# KeyMatrixRev2.net
KiCad netlist of a schematic drawn in Altium Designer
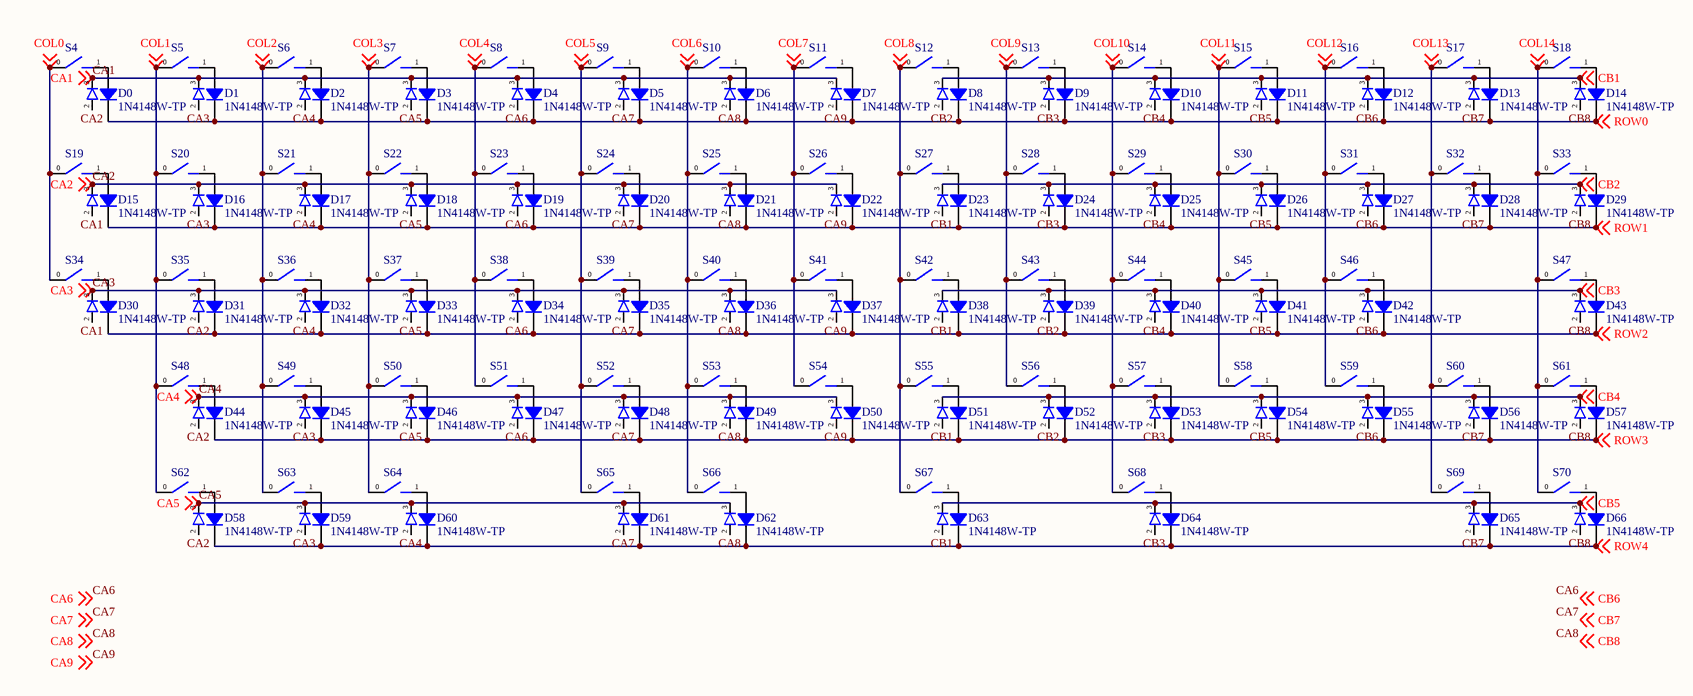
[diagram p0: KeyMatrixRev2.SchDoc]

(export (version "E")
  (design (tool "Eeschema 10.0.6"))
  (components
    (comp (ref "D0")
      (value "1N4148W-TP")
      (footprint "SOD-123")
      (description "DIODE GEN PURP 100V 150MA SOD123")
      (fields (field (name "MANUFACTURER") "Micro Commercial Co"))
      (libsource (lib "Celestial Altium Library - altium_library") (part "Diode"))
    )
    (comp (ref "D1")
      (value "1N4148W-TP")
      (footprint "SOD-123")
      (description "DIODE GEN PURP 100V 150MA SOD123")
      (fields (field (name "MANUFACTURER") "Micro Commercial Co"))
      (libsource (lib "Celestial Altium Library - altium_library") (part "Diode"))
    )
    (comp (ref "D2")
      (value "1N4148W-TP")
      (footprint "SOD-123")
      (description "DIODE GEN PURP 100V 150MA SOD123")
      (fields (field (name "MANUFACTURER") "Micro Commercial Co"))
      (libsource (lib "Celestial Altium Library - altium_library") (part "Diode"))
    )
    (comp (ref "D3")
      (value "1N4148W-TP")
      (footprint "SOD-123")
      (description "DIODE GEN PURP 100V 150MA SOD123")
      (fields (field (name "MANUFACTURER") "Micro Commercial Co"))
      (libsource (lib "Celestial Altium Library - altium_library") (part "Diode"))
    )
    (comp (ref "D4")
      (value "1N4148W-TP")
      (footprint "SOD-123")
      (description "DIODE GEN PURP 100V 150MA SOD123")
      (fields (field (name "MANUFACTURER") "Micro Commercial Co"))
      (libsource (lib "Celestial Altium Library - altium_library") (part "Diode"))
    )
    (comp (ref "D5")
      (value "1N4148W-TP")
      (footprint "SOD-123")
      (description "DIODE GEN PURP 100V 150MA SOD123")
      (fields (field (name "MANUFACTURER") "Micro Commercial Co"))
      (libsource (lib "Celestial Altium Library - altium_library") (part "Diode"))
    )
    (comp (ref "D6")
      (value "1N4148W-TP")
      (footprint "SOD-123")
      (description "DIODE GEN PURP 100V 150MA SOD123")
      (fields (field (name "MANUFACTURER") "Micro Commercial Co"))
      (libsource (lib "Celestial Altium Library - altium_library") (part "Diode"))
    )
    (comp (ref "D7")
      (value "1N4148W-TP")
      (footprint "SOD-123")
      (description "DIODE GEN PURP 100V 150MA SOD123")
      (fields (field (name "MANUFACTURER") "Micro Commercial Co"))
      (libsource (lib "Celestial Altium Library - altium_library") (part "Diode"))
    )
    (comp (ref "D8")
      (value "1N4148W-TP")
      (footprint "SOD-123")
      (description "DIODE GEN PURP 100V 150MA SOD123")
      (fields (field (name "MANUFACTURER") "Micro Commercial Co"))
      (libsource (lib "Celestial Altium Library - altium_library") (part "Diode"))
    )
    (comp (ref "D9")
      (value "1N4148W-TP")
      (footprint "SOD-123")
      (description "DIODE GEN PURP 100V 150MA SOD123")
      (fields (field (name "MANUFACTURER") "Micro Commercial Co"))
      (libsource (lib "Celestial Altium Library - altium_library") (part "Diode"))
    )
    (comp (ref "D10")
      (value "1N4148W-TP")
      (footprint "SOD-123")
      (description "DIODE GEN PURP 100V 150MA SOD123")
      (fields (field (name "MANUFACTURER") "Micro Commercial Co"))
      (libsource (lib "Celestial Altium Library - altium_library") (part "Diode"))
    )
    (comp (ref "D11")
      (value "1N4148W-TP")
      (footprint "SOD-123")
      (description "DIODE GEN PURP 100V 150MA SOD123")
      (fields (field (name "MANUFACTURER") "Micro Commercial Co"))
      (libsource (lib "Celestial Altium Library - altium_library") (part "Diode"))
    )
    (comp (ref "D12")
      (value "1N4148W-TP")
      (footprint "SOD-123")
      (description "DIODE GEN PURP 100V 150MA SOD123")
      (fields (field (name "MANUFACTURER") "Micro Commercial Co"))
      (libsource (lib "Celestial Altium Library - altium_library") (part "Diode"))
    )
    (comp (ref "D13")
      (value "1N4148W-TP")
      (footprint "SOD-123")
      (description "DIODE GEN PURP 100V 150MA SOD123")
      (fields (field (name "MANUFACTURER") "Micro Commercial Co"))
      (libsource (lib "Celestial Altium Library - altium_library") (part "Diode"))
    )
    (comp (ref "D14")
      (value "1N4148W-TP")
      (footprint "SOD-123")
      (description "DIODE GEN PURP 100V 150MA SOD123")
      (fields (field (name "MANUFACTURER") "Micro Commercial Co"))
      (libsource (lib "Celestial Altium Library - altium_library") (part "Diode"))
    )
    (comp (ref "D15")
      (value "1N4148W-TP")
      (footprint "SOD-123")
      (description "DIODE GEN PURP 100V 150MA SOD123")
      (fields (field (name "MANUFACTURER") "Micro Commercial Co"))
      (libsource (lib "Celestial Altium Library - altium_library") (part "Diode"))
    )
    (comp (ref "D16")
      (value "1N4148W-TP")
      (footprint "SOD-123")
      (description "DIODE GEN PURP 100V 150MA SOD123")
      (fields (field (name "MANUFACTURER") "Micro Commercial Co"))
      (libsource (lib "Celestial Altium Library - altium_library") (part "Diode"))
    )
    (comp (ref "D17")
      (value "1N4148W-TP")
      (footprint "SOD-123")
      (description "DIODE GEN PURP 100V 150MA SOD123")
      (fields (field (name "MANUFACTURER") "Micro Commercial Co"))
      (libsource (lib "Celestial Altium Library - altium_library") (part "Diode"))
    )
    (comp (ref "D18")
      (value "1N4148W-TP")
      (footprint "SOD-123")
      (description "DIODE GEN PURP 100V 150MA SOD123")
      (fields (field (name "MANUFACTURER") "Micro Commercial Co"))
      (libsource (lib "Celestial Altium Library - altium_library") (part "Diode"))
    )
    (comp (ref "D19")
      (value "1N4148W-TP")
      (footprint "SOD-123")
      (description "DIODE GEN PURP 100V 150MA SOD123")
      (fields (field (name "MANUFACTURER") "Micro Commercial Co"))
      (libsource (lib "Celestial Altium Library - altium_library") (part "Diode"))
    )
    (comp (ref "D20")
      (value "1N4148W-TP")
      (footprint "SOD-123")
      (description "DIODE GEN PURP 100V 150MA SOD123")
      (fields (field (name "MANUFACTURER") "Micro Commercial Co"))
      (libsource (lib "Celestial Altium Library - altium_library") (part "Diode"))
    )
    (comp (ref "D21")
      (value "1N4148W-TP")
      (footprint "SOD-123")
      (description "DIODE GEN PURP 100V 150MA SOD123")
      (fields (field (name "MANUFACTURER") "Micro Commercial Co"))
      (libsource (lib "Celestial Altium Library - altium_library") (part "Diode"))
    )
    (comp (ref "D22")
      (value "1N4148W-TP")
      (footprint "SOD-123")
      (description "DIODE GEN PURP 100V 150MA SOD123")
      (fields (field (name "MANUFACTURER") "Micro Commercial Co"))
      (libsource (lib "Celestial Altium Library - altium_library") (part "Diode"))
    )
    (comp (ref "D23")
      (value "1N4148W-TP")
      (footprint "SOD-123")
      (description "DIODE GEN PURP 100V 150MA SOD123")
      (fields (field (name "MANUFACTURER") "Micro Commercial Co"))
      (libsource (lib "Celestial Altium Library - altium_library") (part "Diode"))
    )
    (comp (ref "D24")
      (value "1N4148W-TP")
      (footprint "SOD-123")
      (description "DIODE GEN PURP 100V 150MA SOD123")
      (fields (field (name "MANUFACTURER") "Micro Commercial Co"))
      (libsource (lib "Celestial Altium Library - altium_library") (part "Diode"))
    )
    (comp (ref "D25")
      (value "1N4148W-TP")
      (footprint "SOD-123")
      (description "DIODE GEN PURP 100V 150MA SOD123")
      (fields (field (name "MANUFACTURER") "Micro Commercial Co"))
      (libsource (lib "Celestial Altium Library - altium_library") (part "Diode"))
    )
    (comp (ref "D26")
      (value "1N4148W-TP")
      (footprint "SOD-123")
      (description "DIODE GEN PURP 100V 150MA SOD123")
      (fields (field (name "MANUFACTURER") "Micro Commercial Co"))
      (libsource (lib "Celestial Altium Library - altium_library") (part "Diode"))
    )
    (comp (ref "D27")
      (value "1N4148W-TP")
      (footprint "SOD-123")
      (description "DIODE GEN PURP 100V 150MA SOD123")
      (fields (field (name "MANUFACTURER") "Micro Commercial Co"))
      (libsource (lib "Celestial Altium Library - altium_library") (part "Diode"))
    )
    (comp (ref "D28")
      (value "1N4148W-TP")
      (footprint "SOD-123")
      (description "DIODE GEN PURP 100V 150MA SOD123")
      (fields (field (name "MANUFACTURER") "Micro Commercial Co"))
      (libsource (lib "Celestial Altium Library - altium_library") (part "Diode"))
    )
    (comp (ref "D29")
      (value "1N4148W-TP")
      (footprint "SOD-123")
      (description "DIODE GEN PURP 100V 150MA SOD123")
      (fields (field (name "MANUFACTURER") "Micro Commercial Co"))
      (libsource (lib "Celestial Altium Library - altium_library") (part "Diode"))
    )
    (comp (ref "D30")
      (value "1N4148W-TP")
      (footprint "SOD-123")
      (description "DIODE GEN PURP 100V 150MA SOD123")
      (fields (field (name "MANUFACTURER") "Micro Commercial Co"))
      (libsource (lib "Celestial Altium Library - altium_library") (part "Diode"))
    )
    (comp (ref "D31")
      (value "1N4148W-TP")
      (footprint "SOD-123")
      (description "DIODE GEN PURP 100V 150MA SOD123")
      (fields (field (name "MANUFACTURER") "Micro Commercial Co"))
      (libsource (lib "Celestial Altium Library - altium_library") (part "Diode"))
    )
    (comp (ref "D32")
      (value "1N4148W-TP")
      (footprint "SOD-123")
      (description "DIODE GEN PURP 100V 150MA SOD123")
      (fields (field (name "MANUFACTURER") "Micro Commercial Co"))
      (libsource (lib "Celestial Altium Library - altium_library") (part "Diode"))
    )
    (comp (ref "D33")
      (value "1N4148W-TP")
      (footprint "SOD-123")
      (description "DIODE GEN PURP 100V 150MA SOD123")
      (fields (field (name "MANUFACTURER") "Micro Commercial Co"))
      (libsource (lib "Celestial Altium Library - altium_library") (part "Diode"))
    )
    (comp (ref "D34")
      (value "1N4148W-TP")
      (footprint "SOD-123")
      (description "DIODE GEN PURP 100V 150MA SOD123")
      (fields (field (name "MANUFACTURER") "Micro Commercial Co"))
      (libsource (lib "Celestial Altium Library - altium_library") (part "Diode"))
    )
    (comp (ref "D35")
      (value "1N4148W-TP")
      (footprint "SOD-123")
      (description "DIODE GEN PURP 100V 150MA SOD123")
      (fields (field (name "MANUFACTURER") "Micro Commercial Co"))
      (libsource (lib "Celestial Altium Library - altium_library") (part "Diode"))
    )
    (comp (ref "D36")
      (value "1N4148W-TP")
      (footprint "SOD-123")
      (description "DIODE GEN PURP 100V 150MA SOD123")
      (fields (field (name "MANUFACTURER") "Micro Commercial Co"))
      (libsource (lib "Celestial Altium Library - altium_library") (part "Diode"))
    )
    (comp (ref "D37")
      (value "1N4148W-TP")
      (footprint "SOD-123")
      (description "DIODE GEN PURP 100V 150MA SOD123")
      (fields (field (name "MANUFACTURER") "Micro Commercial Co"))
      (libsource (lib "Celestial Altium Library - altium_library") (part "Diode"))
    )
    (comp (ref "D38")
      (value "1N4148W-TP")
      (footprint "SOD-123")
      (description "DIODE GEN PURP 100V 150MA SOD123")
      (fields (field (name "MANUFACTURER") "Micro Commercial Co"))
      (libsource (lib "Celestial Altium Library - altium_library") (part "Diode"))
    )
    (comp (ref "D39")
      (value "1N4148W-TP")
      (footprint "SOD-123")
      (description "DIODE GEN PURP 100V 150MA SOD123")
      (fields (field (name "MANUFACTURER") "Micro Commercial Co"))
      (libsource (lib "Celestial Altium Library - altium_library") (part "Diode"))
    )
    (comp (ref "D40")
      (value "1N4148W-TP")
      (footprint "SOD-123")
      (description "DIODE GEN PURP 100V 150MA SOD123")
      (fields (field (name "MANUFACTURER") "Micro Commercial Co"))
      (libsource (lib "Celestial Altium Library - altium_library") (part "Diode"))
    )
    (comp (ref "D41")
      (value "1N4148W-TP")
      (footprint "SOD-123")
      (description "DIODE GEN PURP 100V 150MA SOD123")
      (fields (field (name "MANUFACTURER") "Micro Commercial Co"))
      (libsource (lib "Celestial Altium Library - altium_library") (part "Diode"))
    )
    (comp (ref "D42")
      (value "1N4148W-TP")
      (footprint "SOD-123")
      (description "DIODE GEN PURP 100V 150MA SOD123")
      (fields (field (name "MANUFACTURER") "Micro Commercial Co"))
      (libsource (lib "Celestial Altium Library - altium_library") (part "Diode"))
    )
    (comp (ref "D43")
      (value "1N4148W-TP")
      (footprint "SOD-123")
      (description "DIODE GEN PURP 100V 150MA SOD123")
      (fields (field (name "MANUFACTURER") "Micro Commercial Co"))
      (libsource (lib "Celestial Altium Library - altium_library") (part "Diode"))
    )
    (comp (ref "D44")
      (value "1N4148W-TP")
      (footprint "SOD-123")
      (description "DIODE GEN PURP 100V 150MA SOD123")
      (fields (field (name "MANUFACTURER") "Micro Commercial Co"))
      (libsource (lib "Celestial Altium Library - altium_library") (part "Diode"))
    )
    (comp (ref "D45")
      (value "1N4148W-TP")
      (footprint "SOD-123")
      (description "DIODE GEN PURP 100V 150MA SOD123")
      (fields (field (name "MANUFACTURER") "Micro Commercial Co"))
      (libsource (lib "Celestial Altium Library - altium_library") (part "Diode"))
    )
    (comp (ref "D46")
      (value "1N4148W-TP")
      (footprint "SOD-123")
      (description "DIODE GEN PURP 100V 150MA SOD123")
      (fields (field (name "MANUFACTURER") "Micro Commercial Co"))
      (libsource (lib "Celestial Altium Library - altium_library") (part "Diode"))
    )
    (comp (ref "D47")
      (value "1N4148W-TP")
      (footprint "SOD-123")
      (description "DIODE GEN PURP 100V 150MA SOD123")
      (fields (field (name "MANUFACTURER") "Micro Commercial Co"))
      (libsource (lib "Celestial Altium Library - altium_library") (part "Diode"))
    )
    (comp (ref "D48")
      (value "1N4148W-TP")
      (footprint "SOD-123")
      (description "DIODE GEN PURP 100V 150MA SOD123")
      (fields (field (name "MANUFACTURER") "Micro Commercial Co"))
      (libsource (lib "Celestial Altium Library - altium_library") (part "Diode"))
    )
    (comp (ref "D49")
      (value "1N4148W-TP")
      (footprint "SOD-123")
      (description "DIODE GEN PURP 100V 150MA SOD123")
      (fields (field (name "MANUFACTURER") "Micro Commercial Co"))
      (libsource (lib "Celestial Altium Library - altium_library") (part "Diode"))
    )
    (comp (ref "D50")
      (value "1N4148W-TP")
      (footprint "SOD-123")
      (description "DIODE GEN PURP 100V 150MA SOD123")
      (fields (field (name "MANUFACTURER") "Micro Commercial Co"))
      (libsource (lib "Celestial Altium Library - altium_library") (part "Diode"))
    )
    (comp (ref "D51")
      (value "1N4148W-TP")
      (footprint "SOD-123")
      (description "DIODE GEN PURP 100V 150MA SOD123")
      (fields (field (name "MANUFACTURER") "Micro Commercial Co"))
      (libsource (lib "Celestial Altium Library - altium_library") (part "Diode"))
    )
    (comp (ref "D52")
      (value "1N4148W-TP")
      (footprint "SOD-123")
      (description "DIODE GEN PURP 100V 150MA SOD123")
      (fields (field (name "MANUFACTURER") "Micro Commercial Co"))
      (libsource (lib "Celestial Altium Library - altium_library") (part "Diode"))
    )
    (comp (ref "D53")
      (value "1N4148W-TP")
      (footprint "SOD-123")
      (description "DIODE GEN PURP 100V 150MA SOD123")
      (fields (field (name "MANUFACTURER") "Micro Commercial Co"))
      (libsource (lib "Celestial Altium Library - altium_library") (part "Diode"))
    )
    (comp (ref "D54")
      (value "1N4148W-TP")
      (footprint "SOD-123")
      (description "DIODE GEN PURP 100V 150MA SOD123")
      (fields (field (name "MANUFACTURER") "Micro Commercial Co"))
      (libsource (lib "Celestial Altium Library - altium_library") (part "Diode"))
    )
    (comp (ref "D55")
      (value "1N4148W-TP")
      (footprint "SOD-123")
      (description "DIODE GEN PURP 100V 150MA SOD123")
      (fields (field (name "MANUFACTURER") "Micro Commercial Co"))
      (libsource (lib "Celestial Altium Library - altium_library") (part "Diode"))
    )
    (comp (ref "D56")
      (value "1N4148W-TP")
      (footprint "SOD-123")
      (description "DIODE GEN PURP 100V 150MA SOD123")
      (fields (field (name "MANUFACTURER") "Micro Commercial Co"))
      (libsource (lib "Celestial Altium Library - altium_library") (part "Diode"))
    )
    (comp (ref "D57")
      (value "1N4148W-TP")
      (footprint "SOD-123")
      (description "DIODE GEN PURP 100V 150MA SOD123")
      (fields (field (name "MANUFACTURER") "Micro Commercial Co"))
      (libsource (lib "Celestial Altium Library - altium_library") (part "Diode"))
    )
    (comp (ref "D58")
      (value "1N4148W-TP")
      (footprint "SOD-123")
      (description "DIODE GEN PURP 100V 150MA SOD123")
      (fields (field (name "MANUFACTURER") "Micro Commercial Co"))
      (libsource (lib "Celestial Altium Library - altium_library") (part "Diode"))
    )
    (comp (ref "D59")
      (value "1N4148W-TP")
      (footprint "SOD-123")
      (description "DIODE GEN PURP 100V 150MA SOD123")
      (fields (field (name "MANUFACTURER") "Micro Commercial Co"))
      (libsource (lib "Celestial Altium Library - altium_library") (part "Diode"))
    )
    (comp (ref "D60")
      (value "1N4148W-TP")
      (footprint "SOD-123")
      (description "DIODE GEN PURP 100V 150MA SOD123")
      (fields (field (name "MANUFACTURER") "Micro Commercial Co"))
      (libsource (lib "Celestial Altium Library - altium_library") (part "Diode"))
    )
    (comp (ref "D61")
      (value "1N4148W-TP")
      (footprint "SOD-123")
      (description "DIODE GEN PURP 100V 150MA SOD123")
      (fields (field (name "MANUFACTURER") "Micro Commercial Co"))
      (libsource (lib "Celestial Altium Library - altium_library") (part "Diode"))
    )
    (comp (ref "D62")
      (value "1N4148W-TP")
      (footprint "SOD-123")
      (description "DIODE GEN PURP 100V 150MA SOD123")
      (fields (field (name "MANUFACTURER") "Micro Commercial Co"))
      (libsource (lib "Celestial Altium Library - altium_library") (part "Diode"))
    )
    (comp (ref "D63")
      (value "1N4148W-TP")
      (footprint "SOD-123")
      (description "DIODE GEN PURP 100V 150MA SOD123")
      (fields (field (name "MANUFACTURER") "Micro Commercial Co"))
      (libsource (lib "Celestial Altium Library - altium_library") (part "Diode"))
    )
    (comp (ref "D64")
      (value "1N4148W-TP")
      (footprint "SOD-123")
      (description "DIODE GEN PURP 100V 150MA SOD123")
      (fields (field (name "MANUFACTURER") "Micro Commercial Co"))
      (libsource (lib "Celestial Altium Library - altium_library") (part "Diode"))
    )
    (comp (ref "D65")
      (value "1N4148W-TP")
      (footprint "SOD-123")
      (description "DIODE GEN PURP 100V 150MA SOD123")
      (fields (field (name "MANUFACTURER") "Micro Commercial Co"))
      (libsource (lib "Celestial Altium Library - altium_library") (part "Diode"))
    )
    (comp (ref "D66")
      (value "1N4148W-TP")
      (footprint "SOD-123")
      (description "DIODE GEN PURP 100V 150MA SOD123")
      (fields (field (name "MANUFACTURER") "Micro Commercial Co"))
      (libsource (lib "Celestial Altium Library - altium_library") (part "Diode"))
    )
    (comp (ref "S4")
      (value "Cherry")
      (footprint "CHERRY-MX-LED-1U")
      (description "Cherry SPST Keyswitch")
      (libsource (lib "CherryMXLED_Footprints") (part "Cherry_Switch"))
    )
    (comp (ref "S5")
      (value "Cherry")
      (footprint "CHERRY-MX-LED-1U")
      (description "Cherry SPST Keyswitch")
      (libsource (lib "CherryMXLED_Footprints") (part "Cherry_Switch"))
    )
    (comp (ref "S6")
      (value "Cherry")
      (footprint "CHERRY-MX-LED-1U")
      (description "Cherry SPST Keyswitch")
      (libsource (lib "CherryMXLED_Footprints") (part "Cherry_Switch"))
    )
    (comp (ref "S7")
      (value "Cherry")
      (footprint "CHERRY-MX-LED-1U")
      (description "Cherry SPST Keyswitch")
      (libsource (lib "CherryMXLED_Footprints") (part "Cherry_Switch"))
    )
    (comp (ref "S8")
      (value "Cherry")
      (footprint "CHERRY-MX-LED-1U")
      (description "Cherry SPST Keyswitch")
      (libsource (lib "CherryMXLED_Footprints") (part "Cherry_Switch"))
    )
    (comp (ref "S9")
      (value "Cherry")
      (footprint "CHERRY-MX-LED-1U")
      (description "Cherry SPST Keyswitch")
      (libsource (lib "CherryMXLED_Footprints") (part "Cherry_Switch"))
    )
    (comp (ref "S10")
      (value "Cherry")
      (footprint "CHERRY-MX-LED-1U")
      (description "Cherry SPST Keyswitch")
      (libsource (lib "CherryMXLED_Footprints") (part "Cherry_Switch"))
    )
    (comp (ref "S11")
      (value "Cherry")
      (footprint "CHERRY-MX-LED-1U")
      (description "Cherry SPST Keyswitch")
      (libsource (lib "CherryMXLED_Footprints") (part "Cherry_Switch"))
    )
    (comp (ref "S12")
      (value "Cherry")
      (footprint "CHERRY-MX-LED-1U")
      (description "Cherry SPST Keyswitch")
      (libsource (lib "CherryMXLED_Footprints") (part "Cherry_Switch"))
    )
    (comp (ref "S13")
      (value "Cherry")
      (footprint "CHERRY-MX-LED-1U")
      (description "Cherry SPST Keyswitch")
      (libsource (lib "CherryMXLED_Footprints") (part "Cherry_Switch"))
    )
    (comp (ref "S14")
      (value "Cherry")
      (footprint "CHERRY-MX-LED-1U")
      (description "Cherry SPST Keyswitch")
      (libsource (lib "CherryMXLED_Footprints") (part "Cherry_Switch"))
    )
    (comp (ref "S15")
      (value "Cherry")
      (footprint "CHERRY-MX-LED-1U")
      (description "Cherry SPST Keyswitch")
      (libsource (lib "CherryMXLED_Footprints") (part "Cherry_Switch"))
    )
    (comp (ref "S16")
      (value "Cherry")
      (footprint "CHERRY-MX-LED-1U")
      (description "Cherry SPST Keyswitch")
      (libsource (lib "CherryMXLED_Footprints") (part "Cherry_Switch"))
    )
    (comp (ref "S17")
      (value "Cherry")
      (footprint "CHERRY-MX-LED-1U")
      (description "Cherry SPST Keyswitch")
      (libsource (lib "CherryMXLED_Footprints") (part "Cherry_Switch"))
    )
    (comp (ref "S18")
      (value "Cherry")
      (footprint "CHERRY-MX-LED-2U")
      (description "Cherry SPST Keyswitch")
      (libsource (lib "CherryMXLED_Footprints") (part "Cherry_Switch"))
    )
    (comp (ref "S19")
      (value "Cherry")
      (footprint "CHERRY-MX-LED-1U")
      (description "Cherry SPST Keyswitch")
      (libsource (lib "CherryMXLED_Footprints") (part "Cherry_Switch"))
    )
    (comp (ref "S20")
      (value "Cherry")
      (footprint "CHERRY-MX-LED-1.5U")
      (description "Cherry SPST Keyswitch")
      (libsource (lib "CherryMXLED_Footprints") (part "Cherry_Switch"))
    )
    (comp (ref "S21")
      (value "Cherry")
      (footprint "CHERRY-MX-LED-1U")
      (description "Cherry SPST Keyswitch")
      (libsource (lib "CherryMXLED_Footprints") (part "Cherry_Switch"))
    )
    (comp (ref "S22")
      (value "Cherry")
      (footprint "CHERRY-MX-LED-1U")
      (description "Cherry SPST Keyswitch")
      (libsource (lib "CherryMXLED_Footprints") (part "Cherry_Switch"))
    )
    (comp (ref "S23")
      (value "Cherry")
      (footprint "CHERRY-MX-LED-1U")
      (description "Cherry SPST Keyswitch")
      (libsource (lib "CherryMXLED_Footprints") (part "Cherry_Switch"))
    )
    (comp (ref "S24")
      (value "Cherry")
      (footprint "CHERRY-MX-LED-1U")
      (description "Cherry SPST Keyswitch")
      (libsource (lib "CherryMXLED_Footprints") (part "Cherry_Switch"))
    )
    (comp (ref "S25")
      (value "Cherry")
      (footprint "CHERRY-MX-LED-1U")
      (description "Cherry SPST Keyswitch")
      (libsource (lib "CherryMXLED_Footprints") (part "Cherry_Switch"))
    )
    (comp (ref "S26")
      (value "Cherry")
      (footprint "CHERRY-MX-LED-1U")
      (description "Cherry SPST Keyswitch")
      (libsource (lib "CherryMXLED_Footprints") (part "Cherry_Switch"))
    )
    (comp (ref "S27")
      (value "Cherry")
      (footprint "CHERRY-MX-LED-1U")
      (description "Cherry SPST Keyswitch")
      (libsource (lib "CherryMXLED_Footprints") (part "Cherry_Switch"))
    )
    (comp (ref "S28")
      (value "Cherry")
      (footprint "CHERRY-MX-LED-1U")
      (description "Cherry SPST Keyswitch")
      (libsource (lib "CherryMXLED_Footprints") (part "Cherry_Switch"))
    )
    (comp (ref "S29")
      (value "Cherry")
      (footprint "CHERRY-MX-LED-1U")
      (description "Cherry SPST Keyswitch")
      (libsource (lib "CherryMXLED_Footprints") (part "Cherry_Switch"))
    )
    (comp (ref "S30")
      (value "Cherry")
      (footprint "CHERRY-MX-LED-1U")
      (description "Cherry SPST Keyswitch")
      (libsource (lib "CherryMXLED_Footprints") (part "Cherry_Switch"))
    )
    (comp (ref "S31")
      (value "Cherry")
      (footprint "CHERRY-MX-LED-1U")
      (description "Cherry SPST Keyswitch")
      (libsource (lib "CherryMXLED_Footprints") (part "Cherry_Switch"))
    )
    (comp (ref "S32")
      (value "Cherry")
      (footprint "CHERRY-MX-LED-1U")
      (description "Cherry SPST Keyswitch")
      (libsource (lib "CherryMXLED_Footprints") (part "Cherry_Switch"))
    )
    (comp (ref "S33")
      (value "Cherry")
      (footprint "CHERRY-MX-LED-1.5U")
      (description "Cherry SPST Keyswitch")
      (libsource (lib "CherryMXLED_Footprints") (part "Cherry_Switch"))
    )
    (comp (ref "S34")
      (value "Cherry")
      (footprint "CHERRY-MX-LED-1U")
      (description "Cherry SPST Keyswitch")
      (libsource (lib "CherryMXLED_Footprints") (part "Cherry_Switch"))
    )
    (comp (ref "S35")
      (value "Cherry")
      (footprint "CHERRY-MX-LED-1.75U")
      (description "Cherry SPST Keyswitch")
      (libsource (lib "CherryMXLED_Footprints") (part "Cherry_Switch"))
    )
    (comp (ref "S36")
      (value "Cherry")
      (footprint "CHERRY-MX-LED-1U")
      (description "Cherry SPST Keyswitch")
      (libsource (lib "CherryMXLED_Footprints") (part "Cherry_Switch"))
    )
    (comp (ref "S37")
      (value "Cherry")
      (footprint "CHERRY-MX-LED-1U")
      (description "Cherry SPST Keyswitch")
      (libsource (lib "CherryMXLED_Footprints") (part "Cherry_Switch"))
    )
    (comp (ref "S38")
      (value "Cherry")
      (footprint "CHERRY-MX-LED-1U")
      (description "Cherry SPST Keyswitch")
      (libsource (lib "CherryMXLED_Footprints") (part "Cherry_Switch"))
    )
    (comp (ref "S39")
      (value "Cherry")
      (footprint "CHERRY-MX-LED-1U")
      (description "Cherry SPST Keyswitch")
      (libsource (lib "CherryMXLED_Footprints") (part "Cherry_Switch"))
    )
    (comp (ref "S40")
      (value "Cherry")
      (footprint "CHERRY-MX-LED-1U")
      (description "Cherry SPST Keyswitch")
      (libsource (lib "CherryMXLED_Footprints") (part "Cherry_Switch"))
    )
    (comp (ref "S41")
      (value "Cherry")
      (footprint "CHERRY-MX-LED-1U")
      (description "Cherry SPST Keyswitch")
      (libsource (lib "CherryMXLED_Footprints") (part "Cherry_Switch"))
    )
    (comp (ref "S42")
      (value "Cherry")
      (footprint "CHERRY-MX-LED-1U")
      (description "Cherry SPST Keyswitch")
      (libsource (lib "CherryMXLED_Footprints") (part "Cherry_Switch"))
    )
    (comp (ref "S43")
      (value "Cherry")
      (footprint "CHERRY-MX-LED-1U")
      (description "Cherry SPST Keyswitch")
      (libsource (lib "CherryMXLED_Footprints") (part "Cherry_Switch"))
    )
    (comp (ref "S44")
      (value "Cherry")
      (footprint "CHERRY-MX-LED-1U")
      (description "Cherry SPST Keyswitch")
      (libsource (lib "CherryMXLED_Footprints") (part "Cherry_Switch"))
    )
    (comp (ref "S45")
      (value "Cherry")
      (footprint "CHERRY-MX-LED-1U")
      (description "Cherry SPST Keyswitch")
      (libsource (lib "CherryMXLED_Footprints") (part "Cherry_Switch"))
    )
    (comp (ref "S46")
      (value "Cherry")
      (footprint "CHERRY-MX-LED-1U")
      (description "Cherry SPST Keyswitch")
      (libsource (lib "CherryMXLED_Footprints") (part "Cherry_Switch"))
    )
    (comp (ref "S47")
      (value "Cherry")
      (footprint "CHERRY-MX-LED-2.25U")
      (description "Cherry SPST Keyswitch")
      (libsource (lib "CherryMXLED_Footprints") (part "Cherry_Switch"))
    )
    (comp (ref "S48")
      (value "Cherry")
      (footprint "CHERRY-MX-LED-2.25U")
      (description "Cherry SPST Keyswitch")
      (libsource (lib "CherryMXLED_Footprints") (part "Cherry_Switch"))
    )
    (comp (ref "S49")
      (value "Cherry")
      (footprint "CHERRY-MX-LED-1U")
      (description "Cherry SPST Keyswitch")
      (libsource (lib "CherryMXLED_Footprints") (part "Cherry_Switch"))
    )
    (comp (ref "S50")
      (value "Cherry")
      (footprint "CHERRY-MX-LED-1U")
      (description "Cherry SPST Keyswitch")
      (libsource (lib "CherryMXLED_Footprints") (part "Cherry_Switch"))
    )
    (comp (ref "S51")
      (value "Cherry")
      (footprint "CHERRY-MX-LED-1U")
      (description "Cherry SPST Keyswitch")
      (libsource (lib "CherryMXLED_Footprints") (part "Cherry_Switch"))
    )
    (comp (ref "S52")
      (value "Cherry")
      (footprint "CHERRY-MX-LED-1U")
      (description "Cherry SPST Keyswitch")
      (libsource (lib "CherryMXLED_Footprints") (part "Cherry_Switch"))
    )
    (comp (ref "S53")
      (value "Cherry")
      (footprint "CHERRY-MX-LED-1U")
      (description "Cherry SPST Keyswitch")
      (libsource (lib "CherryMXLED_Footprints") (part "Cherry_Switch"))
    )
    (comp (ref "S54")
      (value "Cherry")
      (footprint "CHERRY-MX-LED-1U")
      (description "Cherry SPST Keyswitch")
      (libsource (lib "CherryMXLED_Footprints") (part "Cherry_Switch"))
    )
    (comp (ref "S55")
      (value "Cherry")
      (footprint "CHERRY-MX-LED-1U")
      (description "Cherry SPST Keyswitch")
      (libsource (lib "CherryMXLED_Footprints") (part "Cherry_Switch"))
    )
    (comp (ref "S56")
      (value "Cherry")
      (footprint "CHERRY-MX-LED-1U")
      (description "Cherry SPST Keyswitch")
      (libsource (lib "CherryMXLED_Footprints") (part "Cherry_Switch"))
    )
    (comp (ref "S57")
      (value "Cherry")
      (footprint "CHERRY-MX-LED-1U")
      (description "Cherry SPST Keyswitch")
      (libsource (lib "CherryMXLED_Footprints") (part "Cherry_Switch"))
    )
    (comp (ref "S58")
      (value "Cherry")
      (footprint "CHERRY-MX-LED-1U")
      (description "Cherry SPST Keyswitch")
      (libsource (lib "CherryMXLED_Footprints") (part "Cherry_Switch"))
    )
    (comp (ref "S59")
      (value "Cherry")
      (footprint "CHERRY-MX-LED-1U")
      (description "Cherry SPST Keyswitch")
      (libsource (lib "CherryMXLED_Footprints") (part "Cherry_Switch"))
    )
    (comp (ref "S60")
      (value "Cherry")
      (footprint "CHERRY-MX-LED-1U")
      (description "Cherry SPST Keyswitch")
      (libsource (lib "CherryMXLED_Footprints") (part "Cherry_Switch"))
    )
    (comp (ref "S61")
      (value "Cherry")
      (footprint "CHERRY-MX-LED-1U")
      (description "Cherry SPST Keyswitch")
      (libsource (lib "CherryMXLED_Footprints") (part "Cherry_Switch"))
    )
    (comp (ref "S62")
      (value "Cherry")
      (footprint "CHERRY-MX-LED-1.25U")
      (description "Cherry SPST Keyswitch")
      (libsource (lib "CherryMXLED_Footprints") (part "Cherry_Switch"))
    )
    (comp (ref "S63")
      (value "Cherry")
      (footprint "CHERRY-MX-LED-1.25U")
      (description "Cherry SPST Keyswitch")
      (libsource (lib "CherryMXLED_Footprints") (part "Cherry_Switch"))
    )
    (comp (ref "S64")
      (value "Cherry")
      (footprint "CHERRY-MX-LED-1.5U")
      (description "Cherry SPST Keyswitch")
      (libsource (lib "CherryMXLED_Footprints") (part "Cherry_Switch"))
    )
    (comp (ref "S65")
      (value "Cherry")
      (footprint "CHERRY-MX-LED-2U")
      (description "Cherry SPST Keyswitch")
      (libsource (lib "CherryMXLED_Footprints") (part "Cherry_Switch"))
    )
    (comp (ref "S66")
      (value "Cherry")
      (footprint "CHERRY-MX-LED-1.25U")
      (description "Cherry SPST Keyswitch")
      (libsource (lib "CherryMXLED_Footprints") (part "Cherry_Switch"))
    )
    (comp (ref "S67")
      (value "Cherry")
      (footprint "CHERRY-MX-LED-2.75U")
      (description "Cherry SPST Keyswitch")
      (libsource (lib "CherryMXLED_Footprints") (part "Cherry_Switch"))
    )
    (comp (ref "S68")
      (value "Cherry")
      (footprint "CHERRY-MX-LED-1.5U")
      (description "Cherry SPST Keyswitch")
      (libsource (lib "CherryMXLED_Footprints") (part "Cherry_Switch"))
    )
    (comp (ref "S69")
      (value "Cherry")
      (footprint "CHERRY-MX-LED-1.5U")
      (description "Cherry SPST Keyswitch")
      (libsource (lib "CherryMXLED_Footprints") (part "Cherry_Switch"))
    )
    (comp (ref "S70")
      (value "Cherry")
      (footprint "CHERRY-MX-LED-1.5U")
      (description "Cherry SPST Keyswitch")
      (libsource (lib "CherryMXLED_Footprints") (part "Cherry_Switch"))
    )
  )
  (nets
    (net (code "1") (name "CA1") (class "Default")
      (node (ref "S10") (pin "3") (pinfunction "3_3") (pintype "passive"))
      (node (ref "S11") (pin "3") (pinfunction "3_3") (pintype "passive"))
      (node (ref "S19") (pin "2") (pinfunction "2_2") (pintype "passive"))
      (node (ref "S34") (pin "2") (pinfunction "2_2") (pintype "passive"))
      (node (ref "S4") (pin "3") (pinfunction "3_3") (pintype "passive"))
      (node (ref "S5") (pin "3") (pinfunction "3_3") (pintype "passive"))
      (node (ref "S6") (pin "3") (pinfunction "3_3") (pintype "passive"))
      (node (ref "S7") (pin "3") (pinfunction "3_3") (pintype "passive"))
      (node (ref "S8") (pin "3") (pinfunction "3_3") (pintype "passive"))
      (node (ref "S9") (pin "3") (pinfunction "3_3") (pintype "passive"))
    )
    (net (code "2") (name "CA2") (class "Default")
      (node (ref "S19") (pin "3") (pinfunction "3_3") (pintype "passive"))
      (node (ref "S20") (pin "3") (pinfunction "3_3") (pintype "passive"))
      (node (ref "S21") (pin "3") (pinfunction "3_3") (pintype "passive"))
      (node (ref "S22") (pin "3") (pinfunction "3_3") (pintype "passive"))
      (node (ref "S23") (pin "3") (pinfunction "3_3") (pintype "passive"))
      (node (ref "S24") (pin "3") (pinfunction "3_3") (pintype "passive"))
      (node (ref "S25") (pin "3") (pinfunction "3_3") (pintype "passive"))
      (node (ref "S26") (pin "3") (pinfunction "3_3") (pintype "passive"))
      (node (ref "S35") (pin "2") (pinfunction "2_2") (pintype "passive"))
      (node (ref "S4") (pin "2") (pinfunction "2_2") (pintype "passive"))
      (node (ref "S48") (pin "2") (pinfunction "2_2") (pintype "passive"))
      (node (ref "S62") (pin "2") (pinfunction "2_2") (pintype "passive"))
    )
    (net (code "3") (name "CA3") (class "Default")
      (node (ref "S20") (pin "2") (pinfunction "2_2") (pintype "passive"))
      (node (ref "S34") (pin "3") (pinfunction "3_3") (pintype "passive"))
      (node (ref "S35") (pin "3") (pinfunction "3_3") (pintype "passive"))
      (node (ref "S36") (pin "3") (pinfunction "3_3") (pintype "passive"))
      (node (ref "S37") (pin "3") (pinfunction "3_3") (pintype "passive"))
      (node (ref "S38") (pin "3") (pinfunction "3_3") (pintype "passive"))
      (node (ref "S39") (pin "3") (pinfunction "3_3") (pintype "passive"))
      (node (ref "S40") (pin "3") (pinfunction "3_3") (pintype "passive"))
      (node (ref "S41") (pin "3") (pinfunction "3_3") (pintype "passive"))
      (node (ref "S49") (pin "2") (pinfunction "2_2") (pintype "passive"))
      (node (ref "S5") (pin "2") (pinfunction "2_2") (pintype "passive"))
      (node (ref "S63") (pin "2") (pinfunction "2_2") (pintype "passive"))
    )
    (net (code "4") (name "CA4") (class "Default")
      (node (ref "S21") (pin "2") (pinfunction "2_2") (pintype "passive"))
      (node (ref "S36") (pin "2") (pinfunction "2_2") (pintype "passive"))
      (node (ref "S48") (pin "3") (pinfunction "3_3") (pintype "passive"))
      (node (ref "S49") (pin "3") (pinfunction "3_3") (pintype "passive"))
      (node (ref "S50") (pin "3") (pinfunction "3_3") (pintype "passive"))
      (node (ref "S51") (pin "3") (pinfunction "3_3") (pintype "passive"))
      (node (ref "S52") (pin "3") (pinfunction "3_3") (pintype "passive"))
      (node (ref "S53") (pin "3") (pinfunction "3_3") (pintype "passive"))
      (node (ref "S54") (pin "3") (pinfunction "3_3") (pintype "passive"))
      (node (ref "S6") (pin "2") (pinfunction "2_2") (pintype "passive"))
      (node (ref "S64") (pin "2") (pinfunction "2_2") (pintype "passive"))
    )
    (net (code "5") (name "CA5") (class "Default")
      (node (ref "S22") (pin "2") (pinfunction "2_2") (pintype "passive"))
      (node (ref "S37") (pin "2") (pinfunction "2_2") (pintype "passive"))
      (node (ref "S50") (pin "2") (pinfunction "2_2") (pintype "passive"))
      (node (ref "S62") (pin "3") (pinfunction "3_3") (pintype "passive"))
      (node (ref "S63") (pin "3") (pinfunction "3_3") (pintype "passive"))
      (node (ref "S64") (pin "3") (pinfunction "3_3") (pintype "passive"))
      (node (ref "S65") (pin "3") (pinfunction "3_3") (pintype "passive"))
      (node (ref "S66") (pin "3") (pinfunction "3_3") (pintype "passive"))
      (node (ref "S7") (pin "2") (pinfunction "2_2") (pintype "passive"))
    )
    (net (code "6") (name "CA6") (class "Default")
      (node (ref "S16") (pin "2") (pinfunction "2_2") (pintype "passive"))
      (node (ref "S23") (pin "2") (pinfunction "2_2") (pintype "passive"))
      (node (ref "S31") (pin "2") (pinfunction "2_2") (pintype "passive"))
      (node (ref "S38") (pin "2") (pinfunction "2_2") (pintype "passive"))
      (node (ref "S46") (pin "2") (pinfunction "2_2") (pintype "passive"))
      (node (ref "S51") (pin "2") (pinfunction "2_2") (pintype "passive"))
      (node (ref "S59") (pin "2") (pinfunction "2_2") (pintype "passive"))
      (node (ref "S8") (pin "2") (pinfunction "2_2") (pintype "passive"))
    )
    (net (code "7") (name "CA7") (class "Default")
      (node (ref "S17") (pin "2") (pinfunction "2_2") (pintype "passive"))
      (node (ref "S24") (pin "2") (pinfunction "2_2") (pintype "passive"))
      (node (ref "S32") (pin "2") (pinfunction "2_2") (pintype "passive"))
      (node (ref "S39") (pin "2") (pinfunction "2_2") (pintype "passive"))
      (node (ref "S52") (pin "2") (pinfunction "2_2") (pintype "passive"))
      (node (ref "S60") (pin "2") (pinfunction "2_2") (pintype "passive"))
      (node (ref "S65") (pin "2") (pinfunction "2_2") (pintype "passive"))
      (node (ref "S69") (pin "2") (pinfunction "2_2") (pintype "passive"))
      (node (ref "S9") (pin "2") (pinfunction "2_2") (pintype "passive"))
    )
    (net (code "8") (name "CA8") (class "Default")
      (node (ref "S10") (pin "2") (pinfunction "2_2") (pintype "passive"))
      (node (ref "S18") (pin "2") (pinfunction "2_2") (pintype "passive"))
      (node (ref "S25") (pin "2") (pinfunction "2_2") (pintype "passive"))
      (node (ref "S33") (pin "2") (pinfunction "2_2") (pintype "passive"))
      (node (ref "S40") (pin "2") (pinfunction "2_2") (pintype "passive"))
      (node (ref "S47") (pin "2") (pinfunction "2_2") (pintype "passive"))
      (node (ref "S53") (pin "2") (pinfunction "2_2") (pintype "passive"))
      (node (ref "S61") (pin "2") (pinfunction "2_2") (pintype "passive"))
      (node (ref "S66") (pin "2") (pinfunction "2_2") (pintype "passive"))
      (node (ref "S70") (pin "2") (pinfunction "2_2") (pintype "passive"))
    )
    (net (code "9") (name "CA9") (class "Default")
      (node (ref "S11") (pin "2") (pinfunction "2_2") (pintype "passive"))
      (node (ref "S26") (pin "2") (pinfunction "2_2") (pintype "passive"))
      (node (ref "S41") (pin "2") (pinfunction "2_2") (pintype "passive"))
      (node (ref "S54") (pin "2") (pinfunction "2_2") (pintype "passive"))
    )
    (net (code "10") (name "CB1") (class "Default")
      (node (ref "S12") (pin "3") (pinfunction "3_3") (pintype "passive"))
      (node (ref "S13") (pin "3") (pinfunction "3_3") (pintype "passive"))
      (node (ref "S14") (pin "3") (pinfunction "3_3") (pintype "passive"))
      (node (ref "S15") (pin "3") (pinfunction "3_3") (pintype "passive"))
      (node (ref "S16") (pin "3") (pinfunction "3_3") (pintype "passive"))
      (node (ref "S17") (pin "3") (pinfunction "3_3") (pintype "passive"))
      (node (ref "S18") (pin "3") (pinfunction "3_3") (pintype "passive"))
      (node (ref "S27") (pin "2") (pinfunction "2_2") (pintype "passive"))
      (node (ref "S42") (pin "2") (pinfunction "2_2") (pintype "passive"))
      (node (ref "S55") (pin "2") (pinfunction "2_2") (pintype "passive"))
      (node (ref "S67") (pin "2") (pinfunction "2_2") (pintype "passive"))
    )
    (net (code "11") (name "CB2") (class "Default")
      (node (ref "S12") (pin "2") (pinfunction "2_2") (pintype "passive"))
      (node (ref "S27") (pin "3") (pinfunction "3_3") (pintype "passive"))
      (node (ref "S28") (pin "3") (pinfunction "3_3") (pintype "passive"))
      (node (ref "S29") (pin "3") (pinfunction "3_3") (pintype "passive"))
      (node (ref "S30") (pin "3") (pinfunction "3_3") (pintype "passive"))
      (node (ref "S31") (pin "3") (pinfunction "3_3") (pintype "passive"))
      (node (ref "S32") (pin "3") (pinfunction "3_3") (pintype "passive"))
      (node (ref "S33") (pin "3") (pinfunction "3_3") (pintype "passive"))
      (node (ref "S43") (pin "2") (pinfunction "2_2") (pintype "passive"))
      (node (ref "S56") (pin "2") (pinfunction "2_2") (pintype "passive"))
    )
    (net (code "12") (name "CB3") (class "Default")
      (node (ref "S13") (pin "2") (pinfunction "2_2") (pintype "passive"))
      (node (ref "S28") (pin "2") (pinfunction "2_2") (pintype "passive"))
      (node (ref "S42") (pin "3") (pinfunction "3_3") (pintype "passive"))
      (node (ref "S43") (pin "3") (pinfunction "3_3") (pintype "passive"))
      (node (ref "S44") (pin "3") (pinfunction "3_3") (pintype "passive"))
      (node (ref "S45") (pin "3") (pinfunction "3_3") (pintype "passive"))
      (node (ref "S46") (pin "3") (pinfunction "3_3") (pintype "passive"))
      (node (ref "S47") (pin "3") (pinfunction "3_3") (pintype "passive"))
      (node (ref "S57") (pin "2") (pinfunction "2_2") (pintype "passive"))
      (node (ref "S68") (pin "2") (pinfunction "2_2") (pintype "passive"))
    )
    (net (code "13") (name "CB4") (class "Default")
      (node (ref "S14") (pin "2") (pinfunction "2_2") (pintype "passive"))
      (node (ref "S29") (pin "2") (pinfunction "2_2") (pintype "passive"))
      (node (ref "S44") (pin "2") (pinfunction "2_2") (pintype "passive"))
      (node (ref "S55") (pin "3") (pinfunction "3_3") (pintype "passive"))
      (node (ref "S56") (pin "3") (pinfunction "3_3") (pintype "passive"))
      (node (ref "S57") (pin "3") (pinfunction "3_3") (pintype "passive"))
      (node (ref "S58") (pin "3") (pinfunction "3_3") (pintype "passive"))
      (node (ref "S59") (pin "3") (pinfunction "3_3") (pintype "passive"))
      (node (ref "S60") (pin "3") (pinfunction "3_3") (pintype "passive"))
      (node (ref "S61") (pin "3") (pinfunction "3_3") (pintype "passive"))
    )
    (net (code "14") (name "CB5") (class "Default")
      (node (ref "S15") (pin "2") (pinfunction "2_2") (pintype "passive"))
      (node (ref "S30") (pin "2") (pinfunction "2_2") (pintype "passive"))
      (node (ref "S45") (pin "2") (pinfunction "2_2") (pintype "passive"))
      (node (ref "S58") (pin "2") (pinfunction "2_2") (pintype "passive"))
      (node (ref "S67") (pin "3") (pinfunction "3_3") (pintype "passive"))
      (node (ref "S68") (pin "3") (pinfunction "3_3") (pintype "passive"))
      (node (ref "S69") (pin "3") (pinfunction "3_3") (pintype "passive"))
      (node (ref "S70") (pin "3") (pinfunction "3_3") (pintype "passive"))
    )
    (net (code "15") (name "COL0") (class "Default")
      (node (ref "S19") (pin "0") (pinfunction "0_0") (pintype "passive"))
      (node (ref "S34") (pin "0") (pinfunction "0_0") (pintype "passive"))
      (node (ref "S4") (pin "0") (pinfunction "0_0") (pintype "passive"))
    )
    (net (code "16") (name "COL1") (class "Default")
      (node (ref "S20") (pin "0") (pinfunction "0_0") (pintype "passive"))
      (node (ref "S35") (pin "0") (pinfunction "0_0") (pintype "passive"))
      (node (ref "S48") (pin "0") (pinfunction "0_0") (pintype "passive"))
      (node (ref "S5") (pin "0") (pinfunction "0_0") (pintype "passive"))
      (node (ref "S62") (pin "0") (pinfunction "0_0") (pintype "passive"))
    )
    (net (code "17") (name "COL2") (class "Default")
      (node (ref "S21") (pin "0") (pinfunction "0_0") (pintype "passive"))
      (node (ref "S36") (pin "0") (pinfunction "0_0") (pintype "passive"))
      (node (ref "S49") (pin "0") (pinfunction "0_0") (pintype "passive"))
      (node (ref "S6") (pin "0") (pinfunction "0_0") (pintype "passive"))
      (node (ref "S63") (pin "0") (pinfunction "0_0") (pintype "passive"))
    )
    (net (code "18") (name "COL3") (class "Default")
      (node (ref "S22") (pin "0") (pinfunction "0_0") (pintype "passive"))
      (node (ref "S37") (pin "0") (pinfunction "0_0") (pintype "passive"))
      (node (ref "S50") (pin "0") (pinfunction "0_0") (pintype "passive"))
      (node (ref "S64") (pin "0") (pinfunction "0_0") (pintype "passive"))
      (node (ref "S7") (pin "0") (pinfunction "0_0") (pintype "passive"))
    )
    (net (code "19") (name "COL4") (class "Default")
      (node (ref "S23") (pin "0") (pinfunction "0_0") (pintype "passive"))
      (node (ref "S38") (pin "0") (pinfunction "0_0") (pintype "passive"))
      (node (ref "S51") (pin "0") (pinfunction "0_0") (pintype "passive"))
      (node (ref "S8") (pin "0") (pinfunction "0_0") (pintype "passive"))
    )
    (net (code "20") (name "COL5") (class "Default")
      (node (ref "S24") (pin "0") (pinfunction "0_0") (pintype "passive"))
      (node (ref "S39") (pin "0") (pinfunction "0_0") (pintype "passive"))
      (node (ref "S52") (pin "0") (pinfunction "0_0") (pintype "passive"))
      (node (ref "S65") (pin "0") (pinfunction "0_0") (pintype "passive"))
      (node (ref "S9") (pin "0") (pinfunction "0_0") (pintype "passive"))
    )
    (net (code "21") (name "COL6") (class "Default")
      (node (ref "S10") (pin "0") (pinfunction "0_0") (pintype "passive"))
      (node (ref "S25") (pin "0") (pinfunction "0_0") (pintype "passive"))
      (node (ref "S40") (pin "0") (pinfunction "0_0") (pintype "passive"))
      (node (ref "S53") (pin "0") (pinfunction "0_0") (pintype "passive"))
      (node (ref "S66") (pin "0") (pinfunction "0_0") (pintype "passive"))
    )
    (net (code "22") (name "COL7") (class "Default")
      (node (ref "S11") (pin "0") (pinfunction "0_0") (pintype "passive"))
      (node (ref "S26") (pin "0") (pinfunction "0_0") (pintype "passive"))
      (node (ref "S41") (pin "0") (pinfunction "0_0") (pintype "passive"))
      (node (ref "S54") (pin "0") (pinfunction "0_0") (pintype "passive"))
    )
    (net (code "23") (name "COL8") (class "Default")
      (node (ref "S12") (pin "0") (pinfunction "0_0") (pintype "passive"))
      (node (ref "S27") (pin "0") (pinfunction "0_0") (pintype "passive"))
      (node (ref "S42") (pin "0") (pinfunction "0_0") (pintype "passive"))
      (node (ref "S55") (pin "0") (pinfunction "0_0") (pintype "passive"))
      (node (ref "S67") (pin "0") (pinfunction "0_0") (pintype "passive"))
    )
    (net (code "24") (name "COL9") (class "Default")
      (node (ref "S13") (pin "0") (pinfunction "0_0") (pintype "passive"))
      (node (ref "S28") (pin "0") (pinfunction "0_0") (pintype "passive"))
      (node (ref "S43") (pin "0") (pinfunction "0_0") (pintype "passive"))
      (node (ref "S56") (pin "0") (pinfunction "0_0") (pintype "passive"))
    )
    (net (code "25") (name "COL10") (class "Default")
      (node (ref "S14") (pin "0") (pinfunction "0_0") (pintype "passive"))
      (node (ref "S29") (pin "0") (pinfunction "0_0") (pintype "passive"))
      (node (ref "S44") (pin "0") (pinfunction "0_0") (pintype "passive"))
      (node (ref "S57") (pin "0") (pinfunction "0_0") (pintype "passive"))
      (node (ref "S68") (pin "0") (pinfunction "0_0") (pintype "passive"))
    )
    (net (code "26") (name "COL11") (class "Default")
      (node (ref "S15") (pin "0") (pinfunction "0_0") (pintype "passive"))
      (node (ref "S30") (pin "0") (pinfunction "0_0") (pintype "passive"))
      (node (ref "S45") (pin "0") (pinfunction "0_0") (pintype "passive"))
      (node (ref "S58") (pin "0") (pinfunction "0_0") (pintype "passive"))
    )
    (net (code "27") (name "COL12") (class "Default")
      (node (ref "S16") (pin "0") (pinfunction "0_0") (pintype "passive"))
      (node (ref "S31") (pin "0") (pinfunction "0_0") (pintype "passive"))
      (node (ref "S46") (pin "0") (pinfunction "0_0") (pintype "passive"))
      (node (ref "S59") (pin "0") (pinfunction "0_0") (pintype "passive"))
    )
    (net (code "28") (name "COL13") (class "Default")
      (node (ref "S17") (pin "0") (pinfunction "0_0") (pintype "passive"))
      (node (ref "S32") (pin "0") (pinfunction "0_0") (pintype "passive"))
      (node (ref "S60") (pin "0") (pinfunction "0_0") (pintype "passive"))
      (node (ref "S69") (pin "0") (pinfunction "0_0") (pintype "passive"))
    )
    (net (code "29") (name "COL14") (class "Default")
      (node (ref "S18") (pin "0") (pinfunction "0_0") (pintype "passive"))
      (node (ref "S33") (pin "0") (pinfunction "0_0") (pintype "passive"))
      (node (ref "S47") (pin "0") (pinfunction "0_0") (pintype "passive"))
      (node (ref "S61") (pin "0") (pinfunction "0_0") (pintype "passive"))
      (node (ref "S70") (pin "0") (pinfunction "0_0") (pintype "passive"))
    )
    (net (code "30") (name "Net-(D0-Pad1)") (class "Default")
      (node (ref "D0") (pin "1") (pinfunction "1_1") (pintype "passive"))
      (node (ref "S4") (pin "1") (pinfunction "1_1") (pintype "passive"))
    )
    (net (code "31") (name "Net-(D1-Pad1)") (class "Default")
      (node (ref "D1") (pin "1") (pinfunction "1_1") (pintype "passive"))
      (node (ref "S5") (pin "1") (pinfunction "1_1") (pintype "passive"))
    )
    (net (code "32") (name "Net-(D2-Pad1)") (class "Default")
      (node (ref "D2") (pin "1") (pinfunction "1_1") (pintype "passive"))
      (node (ref "S6") (pin "1") (pinfunction "1_1") (pintype "passive"))
    )
    (net (code "33") (name "Net-(D3-Pad1)") (class "Default")
      (node (ref "D3") (pin "1") (pinfunction "1_1") (pintype "passive"))
      (node (ref "S7") (pin "1") (pinfunction "1_1") (pintype "passive"))
    )
    (net (code "34") (name "Net-(D4-Pad1)") (class "Default")
      (node (ref "D4") (pin "1") (pinfunction "1_1") (pintype "passive"))
      (node (ref "S8") (pin "1") (pinfunction "1_1") (pintype "passive"))
    )
    (net (code "35") (name "Net-(D5-Pad1)") (class "Default")
      (node (ref "D5") (pin "1") (pinfunction "1_1") (pintype "passive"))
      (node (ref "S9") (pin "1") (pinfunction "1_1") (pintype "passive"))
    )
    (net (code "36") (name "Net-(D6-Pad1)") (class "Default")
      (node (ref "D6") (pin "1") (pinfunction "1_1") (pintype "passive"))
      (node (ref "S10") (pin "1") (pinfunction "1_1") (pintype "passive"))
    )
    (net (code "37") (name "Net-(D7-Pad1)") (class "Default")
      (node (ref "D7") (pin "1") (pinfunction "1_1") (pintype "passive"))
      (node (ref "S11") (pin "1") (pinfunction "1_1") (pintype "passive"))
    )
    (net (code "38") (name "Net-(D8-Pad1)") (class "Default")
      (node (ref "D8") (pin "1") (pinfunction "1_1") (pintype "passive"))
      (node (ref "S12") (pin "1") (pinfunction "1_1") (pintype "passive"))
    )
    (net (code "39") (name "Net-(D9-Pad1)") (class "Default")
      (node (ref "D9") (pin "1") (pinfunction "1_1") (pintype "passive"))
      (node (ref "S13") (pin "1") (pinfunction "1_1") (pintype "passive"))
    )
    (net (code "40") (name "Net-(D10-Pad1)") (class "Default")
      (node (ref "D10") (pin "1") (pinfunction "1_1") (pintype "passive"))
      (node (ref "S14") (pin "1") (pinfunction "1_1") (pintype "passive"))
    )
    (net (code "41") (name "Net-(D11-Pad1)") (class "Default")
      (node (ref "D11") (pin "1") (pinfunction "1_1") (pintype "passive"))
      (node (ref "S15") (pin "1") (pinfunction "1_1") (pintype "passive"))
    )
    (net (code "42") (name "Net-(D12-Pad1)") (class "Default")
      (node (ref "D12") (pin "1") (pinfunction "1_1") (pintype "passive"))
      (node (ref "S16") (pin "1") (pinfunction "1_1") (pintype "passive"))
    )
    (net (code "43") (name "Net-(D13-Pad1)") (class "Default")
      (node (ref "D13") (pin "1") (pinfunction "1_1") (pintype "passive"))
      (node (ref "S17") (pin "1") (pinfunction "1_1") (pintype "passive"))
    )
    (net (code "44") (name "Net-(D14-Pad1)") (class "Default")
      (node (ref "D14") (pin "1") (pinfunction "1_1") (pintype "passive"))
      (node (ref "S18") (pin "1") (pinfunction "1_1") (pintype "passive"))
    )
    (net (code "45") (name "Net-(D15-Pad1)") (class "Default")
      (node (ref "D15") (pin "1") (pinfunction "1_1") (pintype "passive"))
      (node (ref "S19") (pin "1") (pinfunction "1_1") (pintype "passive"))
    )
    (net (code "46") (name "Net-(D16-Pad1)") (class "Default")
      (node (ref "D16") (pin "1") (pinfunction "1_1") (pintype "passive"))
      (node (ref "S20") (pin "1") (pinfunction "1_1") (pintype "passive"))
    )
    (net (code "47") (name "Net-(D17-Pad1)") (class "Default")
      (node (ref "D17") (pin "1") (pinfunction "1_1") (pintype "passive"))
      (node (ref "S21") (pin "1") (pinfunction "1_1") (pintype "passive"))
    )
    (net (code "48") (name "Net-(D18-Pad1)") (class "Default")
      (node (ref "D18") (pin "1") (pinfunction "1_1") (pintype "passive"))
      (node (ref "S22") (pin "1") (pinfunction "1_1") (pintype "passive"))
    )
    (net (code "49") (name "Net-(D19-Pad1)") (class "Default")
      (node (ref "D19") (pin "1") (pinfunction "1_1") (pintype "passive"))
      (node (ref "S23") (pin "1") (pinfunction "1_1") (pintype "passive"))
    )
    (net (code "50") (name "Net-(D20-Pad1)") (class "Default")
      (node (ref "D20") (pin "1") (pinfunction "1_1") (pintype "passive"))
      (node (ref "S24") (pin "1") (pinfunction "1_1") (pintype "passive"))
    )
    (net (code "51") (name "Net-(D21-Pad1)") (class "Default")
      (node (ref "D21") (pin "1") (pinfunction "1_1") (pintype "passive"))
      (node (ref "S25") (pin "1") (pinfunction "1_1") (pintype "passive"))
    )
    (net (code "52") (name "Net-(D22-Pad1)") (class "Default")
      (node (ref "D22") (pin "1") (pinfunction "1_1") (pintype "passive"))
      (node (ref "S26") (pin "1") (pinfunction "1_1") (pintype "passive"))
    )
    (net (code "53") (name "Net-(D23-Pad1)") (class "Default")
      (node (ref "D23") (pin "1") (pinfunction "1_1") (pintype "passive"))
      (node (ref "S27") (pin "1") (pinfunction "1_1") (pintype "passive"))
    )
    (net (code "54") (name "Net-(D24-Pad1)") (class "Default")
      (node (ref "D24") (pin "1") (pinfunction "1_1") (pintype "passive"))
      (node (ref "S28") (pin "1") (pinfunction "1_1") (pintype "passive"))
    )
    (net (code "55") (name "Net-(D25-Pad1)") (class "Default")
      (node (ref "D25") (pin "1") (pinfunction "1_1") (pintype "passive"))
      (node (ref "S29") (pin "1") (pinfunction "1_1") (pintype "passive"))
    )
    (net (code "56") (name "Net-(D26-Pad1)") (class "Default")
      (node (ref "D26") (pin "1") (pinfunction "1_1") (pintype "passive"))
      (node (ref "S30") (pin "1") (pinfunction "1_1") (pintype "passive"))
    )
    (net (code "57") (name "Net-(D27-Pad1)") (class "Default")
      (node (ref "D27") (pin "1") (pinfunction "1_1") (pintype "passive"))
      (node (ref "S31") (pin "1") (pinfunction "1_1") (pintype "passive"))
    )
    (net (code "58") (name "Net-(D28-Pad1)") (class "Default")
      (node (ref "D28") (pin "1") (pinfunction "1_1") (pintype "passive"))
      (node (ref "S32") (pin "1") (pinfunction "1_1") (pintype "passive"))
    )
    (net (code "59") (name "Net-(D29-Pad1)") (class "Default")
      (node (ref "D29") (pin "1") (pinfunction "1_1") (pintype "passive"))
      (node (ref "S33") (pin "1") (pinfunction "1_1") (pintype "passive"))
    )
    (net (code "60") (name "Net-(D30-Pad1)") (class "Default")
      (node (ref "D30") (pin "1") (pinfunction "1_1") (pintype "passive"))
      (node (ref "S34") (pin "1") (pinfunction "1_1") (pintype "passive"))
    )
    (net (code "61") (name "Net-(D31-Pad1)") (class "Default")
      (node (ref "D31") (pin "1") (pinfunction "1_1") (pintype "passive"))
      (node (ref "S35") (pin "1") (pinfunction "1_1") (pintype "passive"))
    )
    (net (code "62") (name "Net-(D32-Pad1)") (class "Default")
      (node (ref "D32") (pin "1") (pinfunction "1_1") (pintype "passive"))
      (node (ref "S36") (pin "1") (pinfunction "1_1") (pintype "passive"))
    )
    (net (code "63") (name "Net-(D33-Pad1)") (class "Default")
      (node (ref "D33") (pin "1") (pinfunction "1_1") (pintype "passive"))
      (node (ref "S37") (pin "1") (pinfunction "1_1") (pintype "passive"))
    )
    (net (code "64") (name "Net-(D34-Pad1)") (class "Default")
      (node (ref "D34") (pin "1") (pinfunction "1_1") (pintype "passive"))
      (node (ref "S38") (pin "1") (pinfunction "1_1") (pintype "passive"))
    )
    (net (code "65") (name "Net-(D35-Pad1)") (class "Default")
      (node (ref "D35") (pin "1") (pinfunction "1_1") (pintype "passive"))
      (node (ref "S39") (pin "1") (pinfunction "1_1") (pintype "passive"))
    )
    (net (code "66") (name "Net-(D36-Pad1)") (class "Default")
      (node (ref "D36") (pin "1") (pinfunction "1_1") (pintype "passive"))
      (node (ref "S40") (pin "1") (pinfunction "1_1") (pintype "passive"))
    )
    (net (code "67") (name "Net-(D37-Pad1)") (class "Default")
      (node (ref "D37") (pin "1") (pinfunction "1_1") (pintype "passive"))
      (node (ref "S41") (pin "1") (pinfunction "1_1") (pintype "passive"))
    )
    (net (code "68") (name "Net-(D38-Pad1)") (class "Default")
      (node (ref "D38") (pin "1") (pinfunction "1_1") (pintype "passive"))
      (node (ref "S42") (pin "1") (pinfunction "1_1") (pintype "passive"))
    )
    (net (code "69") (name "Net-(D39-Pad1)") (class "Default")
      (node (ref "D39") (pin "1") (pinfunction "1_1") (pintype "passive"))
      (node (ref "S43") (pin "1") (pinfunction "1_1") (pintype "passive"))
    )
    (net (code "70") (name "Net-(D40-Pad1)") (class "Default")
      (node (ref "D40") (pin "1") (pinfunction "1_1") (pintype "passive"))
      (node (ref "S44") (pin "1") (pinfunction "1_1") (pintype "passive"))
    )
    (net (code "71") (name "Net-(D41-Pad1)") (class "Default")
      (node (ref "D41") (pin "1") (pinfunction "1_1") (pintype "passive"))
      (node (ref "S45") (pin "1") (pinfunction "1_1") (pintype "passive"))
    )
    (net (code "72") (name "Net-(D42-Pad1)") (class "Default")
      (node (ref "D42") (pin "1") (pinfunction "1_1") (pintype "passive"))
      (node (ref "S46") (pin "1") (pinfunction "1_1") (pintype "passive"))
    )
    (net (code "73") (name "Net-(D43-Pad1)") (class "Default")
      (node (ref "D43") (pin "1") (pinfunction "1_1") (pintype "passive"))
      (node (ref "S47") (pin "1") (pinfunction "1_1") (pintype "passive"))
    )
    (net (code "74") (name "Net-(D44-Pad1)") (class "Default")
      (node (ref "D44") (pin "1") (pinfunction "1_1") (pintype "passive"))
      (node (ref "S48") (pin "1") (pinfunction "1_1") (pintype "passive"))
    )
    (net (code "75") (name "Net-(D45-Pad1)") (class "Default")
      (node (ref "D45") (pin "1") (pinfunction "1_1") (pintype "passive"))
      (node (ref "S49") (pin "1") (pinfunction "1_1") (pintype "passive"))
    )
    (net (code "76") (name "Net-(D46-Pad1)") (class "Default")
      (node (ref "D46") (pin "1") (pinfunction "1_1") (pintype "passive"))
      (node (ref "S50") (pin "1") (pinfunction "1_1") (pintype "passive"))
    )
    (net (code "77") (name "Net-(D47-Pad1)") (class "Default")
      (node (ref "D47") (pin "1") (pinfunction "1_1") (pintype "passive"))
      (node (ref "S51") (pin "1") (pinfunction "1_1") (pintype "passive"))
    )
    (net (code "78") (name "Net-(D48-Pad1)") (class "Default")
      (node (ref "D48") (pin "1") (pinfunction "1_1") (pintype "passive"))
      (node (ref "S52") (pin "1") (pinfunction "1_1") (pintype "passive"))
    )
    (net (code "79") (name "Net-(D49-Pad1)") (class "Default")
      (node (ref "D49") (pin "1") (pinfunction "1_1") (pintype "passive"))
      (node (ref "S53") (pin "1") (pinfunction "1_1") (pintype "passive"))
    )
    (net (code "80") (name "Net-(D50-Pad1)") (class "Default")
      (node (ref "D50") (pin "1") (pinfunction "1_1") (pintype "passive"))
      (node (ref "S54") (pin "1") (pinfunction "1_1") (pintype "passive"))
    )
    (net (code "81") (name "Net-(D51-Pad1)") (class "Default")
      (node (ref "D51") (pin "1") (pinfunction "1_1") (pintype "passive"))
      (node (ref "S55") (pin "1") (pinfunction "1_1") (pintype "passive"))
    )
    (net (code "82") (name "Net-(D52-Pad1)") (class "Default")
      (node (ref "D52") (pin "1") (pinfunction "1_1") (pintype "passive"))
      (node (ref "S56") (pin "1") (pinfunction "1_1") (pintype "passive"))
    )
    (net (code "83") (name "Net-(D53-Pad1)") (class "Default")
      (node (ref "D53") (pin "1") (pinfunction "1_1") (pintype "passive"))
      (node (ref "S57") (pin "1") (pinfunction "1_1") (pintype "passive"))
    )
    (net (code "84") (name "Net-(D54-Pad1)") (class "Default")
      (node (ref "D54") (pin "1") (pinfunction "1_1") (pintype "passive"))
      (node (ref "S58") (pin "1") (pinfunction "1_1") (pintype "passive"))
    )
    (net (code "85") (name "Net-(D55-Pad1)") (class "Default")
      (node (ref "D55") (pin "1") (pinfunction "1_1") (pintype "passive"))
      (node (ref "S59") (pin "1") (pinfunction "1_1") (pintype "passive"))
    )
    (net (code "86") (name "Net-(D56-Pad1)") (class "Default")
      (node (ref "D56") (pin "1") (pinfunction "1_1") (pintype "passive"))
      (node (ref "S60") (pin "1") (pinfunction "1_1") (pintype "passive"))
    )
    (net (code "87") (name "Net-(D57-Pad1)") (class "Default")
      (node (ref "D57") (pin "1") (pinfunction "1_1") (pintype "passive"))
      (node (ref "S61") (pin "1") (pinfunction "1_1") (pintype "passive"))
    )
    (net (code "88") (name "Net-(D58-Pad1)") (class "Default")
      (node (ref "D58") (pin "1") (pinfunction "1_1") (pintype "passive"))
      (node (ref "S62") (pin "1") (pinfunction "1_1") (pintype "passive"))
    )
    (net (code "89") (name "Net-(D59-Pad1)") (class "Default")
      (node (ref "D59") (pin "1") (pinfunction "1_1") (pintype "passive"))
      (node (ref "S63") (pin "1") (pinfunction "1_1") (pintype "passive"))
    )
    (net (code "90") (name "Net-(D60-Pad1)") (class "Default")
      (node (ref "D60") (pin "1") (pinfunction "1_1") (pintype "passive"))
      (node (ref "S64") (pin "1") (pinfunction "1_1") (pintype "passive"))
    )
    (net (code "91") (name "Net-(D61-Pad1)") (class "Default")
      (node (ref "D61") (pin "1") (pinfunction "1_1") (pintype "passive"))
      (node (ref "S65") (pin "1") (pinfunction "1_1") (pintype "passive"))
    )
    (net (code "92") (name "Net-(D62-Pad1)") (class "Default")
      (node (ref "D62") (pin "1") (pinfunction "1_1") (pintype "passive"))
      (node (ref "S66") (pin "1") (pinfunction "1_1") (pintype "passive"))
    )
    (net (code "93") (name "Net-(D63-Pad1)") (class "Default")
      (node (ref "D63") (pin "1") (pinfunction "1_1") (pintype "passive"))
      (node (ref "S67") (pin "1") (pinfunction "1_1") (pintype "passive"))
    )
    (net (code "94") (name "Net-(D64-Pad1)") (class "Default")
      (node (ref "D64") (pin "1") (pinfunction "1_1") (pintype "passive"))
      (node (ref "S68") (pin "1") (pinfunction "1_1") (pintype "passive"))
    )
    (net (code "95") (name "Net-(D65-Pad1)") (class "Default")
      (node (ref "D65") (pin "1") (pinfunction "1_1") (pintype "passive"))
      (node (ref "S69") (pin "1") (pinfunction "1_1") (pintype "passive"))
    )
    (net (code "96") (name "Net-(D66-Pad1)") (class "Default")
      (node (ref "D66") (pin "1") (pinfunction "1_1") (pintype "passive"))
      (node (ref "S70") (pin "1") (pinfunction "1_1") (pintype "passive"))
    )
    (net (code "97") (name "ROW0") (class "Default")
      (node (ref "D0") (pin "2") (pinfunction "2_2") (pintype "passive"))
      (node (ref "D1") (pin "2") (pinfunction "2_2") (pintype "passive"))
      (node (ref "D10") (pin "2") (pinfunction "2_2") (pintype "passive"))
      (node (ref "D11") (pin "2") (pinfunction "2_2") (pintype "passive"))
      (node (ref "D12") (pin "2") (pinfunction "2_2") (pintype "passive"))
      (node (ref "D13") (pin "2") (pinfunction "2_2") (pintype "passive"))
      (node (ref "D14") (pin "2") (pinfunction "2_2") (pintype "passive"))
      (node (ref "D2") (pin "2") (pinfunction "2_2") (pintype "passive"))
      (node (ref "D3") (pin "2") (pinfunction "2_2") (pintype "passive"))
      (node (ref "D4") (pin "2") (pinfunction "2_2") (pintype "passive"))
      (node (ref "D5") (pin "2") (pinfunction "2_2") (pintype "passive"))
      (node (ref "D6") (pin "2") (pinfunction "2_2") (pintype "passive"))
      (node (ref "D7") (pin "2") (pinfunction "2_2") (pintype "passive"))
      (node (ref "D8") (pin "2") (pinfunction "2_2") (pintype "passive"))
      (node (ref "D9") (pin "2") (pinfunction "2_2") (pintype "passive"))
    )
    (net (code "98") (name "ROW1") (class "Default")
      (node (ref "D15") (pin "2") (pinfunction "2_2") (pintype "passive"))
      (node (ref "D16") (pin "2") (pinfunction "2_2") (pintype "passive"))
      (node (ref "D17") (pin "2") (pinfunction "2_2") (pintype "passive"))
      (node (ref "D18") (pin "2") (pinfunction "2_2") (pintype "passive"))
      (node (ref "D19") (pin "2") (pinfunction "2_2") (pintype "passive"))
      (node (ref "D20") (pin "2") (pinfunction "2_2") (pintype "passive"))
      (node (ref "D21") (pin "2") (pinfunction "2_2") (pintype "passive"))
      (node (ref "D22") (pin "2") (pinfunction "2_2") (pintype "passive"))
      (node (ref "D23") (pin "2") (pinfunction "2_2") (pintype "passive"))
      (node (ref "D24") (pin "2") (pinfunction "2_2") (pintype "passive"))
      (node (ref "D25") (pin "2") (pinfunction "2_2") (pintype "passive"))
      (node (ref "D26") (pin "2") (pinfunction "2_2") (pintype "passive"))
      (node (ref "D27") (pin "2") (pinfunction "2_2") (pintype "passive"))
      (node (ref "D28") (pin "2") (pinfunction "2_2") (pintype "passive"))
      (node (ref "D29") (pin "2") (pinfunction "2_2") (pintype "passive"))
    )
    (net (code "99") (name "ROW2") (class "Default")
      (node (ref "D30") (pin "2") (pinfunction "2_2") (pintype "passive"))
      (node (ref "D31") (pin "2") (pinfunction "2_2") (pintype "passive"))
      (node (ref "D32") (pin "2") (pinfunction "2_2") (pintype "passive"))
      (node (ref "D33") (pin "2") (pinfunction "2_2") (pintype "passive"))
      (node (ref "D34") (pin "2") (pinfunction "2_2") (pintype "passive"))
      (node (ref "D35") (pin "2") (pinfunction "2_2") (pintype "passive"))
      (node (ref "D36") (pin "2") (pinfunction "2_2") (pintype "passive"))
      (node (ref "D37") (pin "2") (pinfunction "2_2") (pintype "passive"))
      (node (ref "D38") (pin "2") (pinfunction "2_2") (pintype "passive"))
      (node (ref "D39") (pin "2") (pinfunction "2_2") (pintype "passive"))
      (node (ref "D40") (pin "2") (pinfunction "2_2") (pintype "passive"))
      (node (ref "D41") (pin "2") (pinfunction "2_2") (pintype "passive"))
      (node (ref "D42") (pin "2") (pinfunction "2_2") (pintype "passive"))
      (node (ref "D43") (pin "2") (pinfunction "2_2") (pintype "passive"))
    )
    (net (code "100") (name "ROW3") (class "Default")
      (node (ref "D44") (pin "2") (pinfunction "2_2") (pintype "passive"))
      (node (ref "D45") (pin "2") (pinfunction "2_2") (pintype "passive"))
      (node (ref "D46") (pin "2") (pinfunction "2_2") (pintype "passive"))
      (node (ref "D47") (pin "2") (pinfunction "2_2") (pintype "passive"))
      (node (ref "D48") (pin "2") (pinfunction "2_2") (pintype "passive"))
      (node (ref "D49") (pin "2") (pinfunction "2_2") (pintype "passive"))
      (node (ref "D50") (pin "2") (pinfunction "2_2") (pintype "passive"))
      (node (ref "D51") (pin "2") (pinfunction "2_2") (pintype "passive"))
      (node (ref "D52") (pin "2") (pinfunction "2_2") (pintype "passive"))
      (node (ref "D53") (pin "2") (pinfunction "2_2") (pintype "passive"))
      (node (ref "D54") (pin "2") (pinfunction "2_2") (pintype "passive"))
      (node (ref "D55") (pin "2") (pinfunction "2_2") (pintype "passive"))
      (node (ref "D56") (pin "2") (pinfunction "2_2") (pintype "passive"))
      (node (ref "D57") (pin "2") (pinfunction "2_2") (pintype "passive"))
    )
    (net (code "101") (name "ROW4") (class "Default")
      (node (ref "D58") (pin "2") (pinfunction "2_2") (pintype "passive"))
      (node (ref "D59") (pin "2") (pinfunction "2_2") (pintype "passive"))
      (node (ref "D60") (pin "2") (pinfunction "2_2") (pintype "passive"))
      (node (ref "D61") (pin "2") (pinfunction "2_2") (pintype "passive"))
      (node (ref "D62") (pin "2") (pinfunction "2_2") (pintype "passive"))
      (node (ref "D63") (pin "2") (pinfunction "2_2") (pintype "passive"))
      (node (ref "D64") (pin "2") (pinfunction "2_2") (pintype "passive"))
      (node (ref "D65") (pin "2") (pinfunction "2_2") (pintype "passive"))
      (node (ref "D66") (pin "2") (pinfunction "2_2") (pintype "passive"))
    )
  )
)
